# Schematic.net
KiCad netlist of a schematic drawn in EAGLE
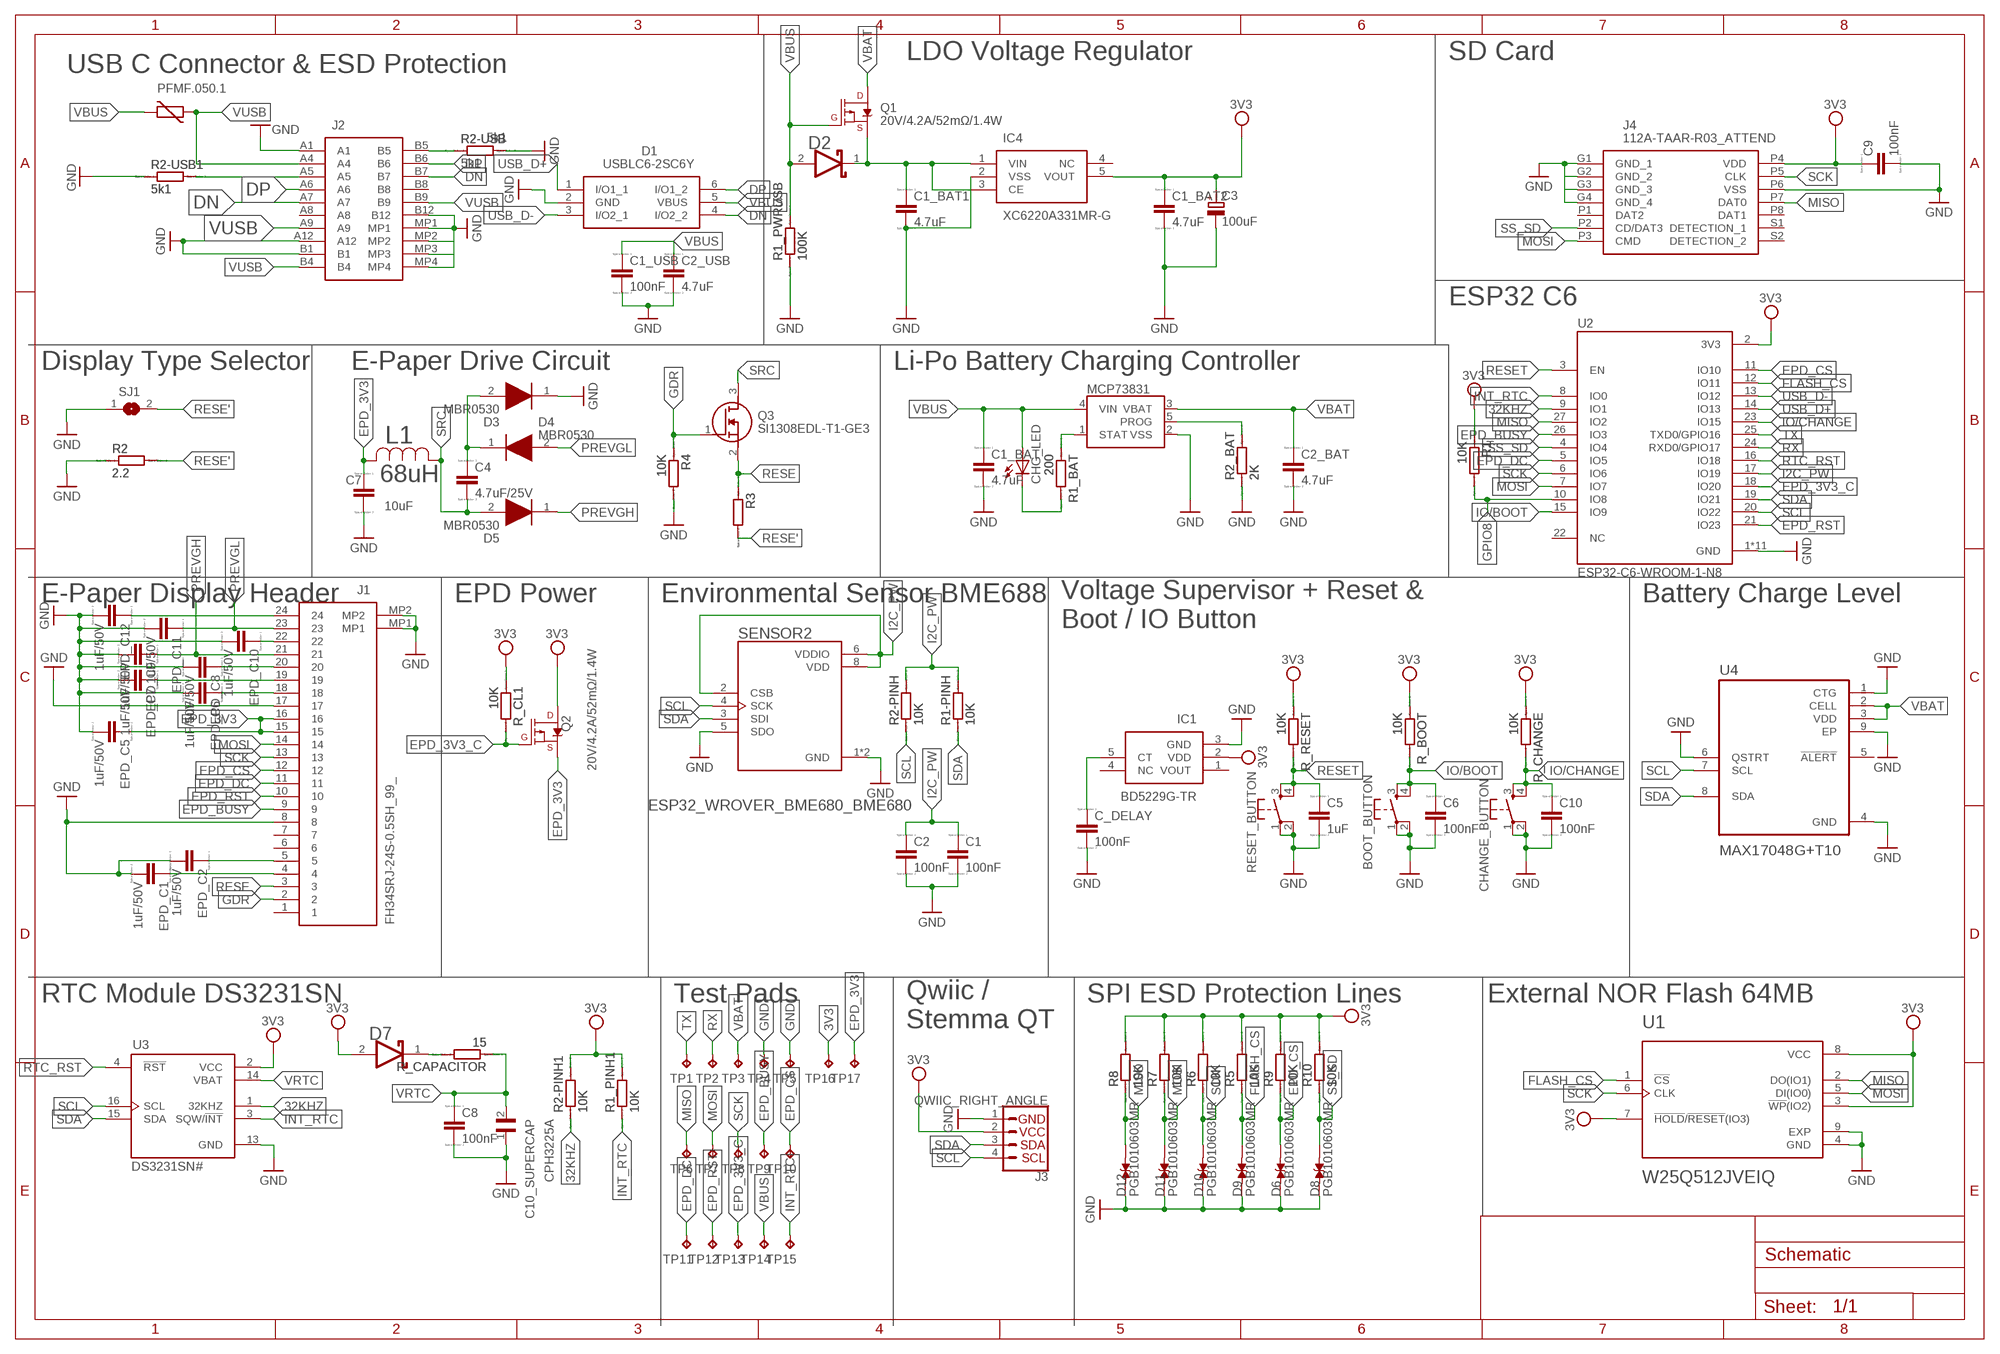
[diagram p0: schematic, sheet 1]

(export (version "E")
  (design (tool "Eeschema 10.0.6"))
  (components
    (comp (ref "BOOT_BUTTON")
      (value "BUTTON_CUSYOMV1")
      (footprint "eagle-import:MYBUTTON")
      (libsource (lib "eagle-import") (part "BUTTON_CUSYOMV1"))
    )
    (comp (ref "C1")
      (value "100nF")
      (footprint "eagle-import:ESP32_WROVER_EAGLE-LTSPICE_C0402")
      (libsource (lib "eagle-import") (part "ESP32_WROVER_EAGLE-LTSPICE_CC0402"))
    )
    (comp (ref "C1_BAT")
      (value "4.7uF")
      (footprint "eagle-import:ESP32_WROVER_EAGLE-LTSPICE_C0402")
      (libsource (lib "eagle-import") (part "ESP32_WROVER_EAGLE-LTSPICE_CC0402"))
    )
    (comp (ref "C1_BAT1")
      (value "4.7uF")
      (footprint "eagle-import:ESP32_WROVER_EAGLE-LTSPICE_C0402")
      (libsource (lib "eagle-import") (part "ESP32_WROVER_EAGLE-LTSPICE_CC0402"))
    )
    (comp (ref "C1_BAT2")
      (value "4.7uF")
      (footprint "eagle-import:ESP32_WROVER_EAGLE-LTSPICE_C0402")
      (libsource (lib "eagle-import") (part "ESP32_WROVER_EAGLE-LTSPICE_CC0402"))
    )
    (comp (ref "C1_USB")
      (value "100nF")
      (footprint "eagle-import:ESP32_WROVER_EAGLE-LTSPICE_C0402")
      (libsource (lib "eagle-import") (part "ESP32_WROVER_EAGLE-LTSPICE_CC0402"))
    )
    (comp (ref "C2")
      (value "100nF")
      (footprint "eagle-import:ESP32_WROVER_EAGLE-LTSPICE_C0402")
      (libsource (lib "eagle-import") (part "ESP32_WROVER_EAGLE-LTSPICE_CC0402"))
    )
    (comp (ref "C2_BAT")
      (value "4.7uF")
      (footprint "eagle-import:ESP32_WROVER_EAGLE-LTSPICE_C0402")
      (libsource (lib "eagle-import") (part "ESP32_WROVER_EAGLE-LTSPICE_CC0402"))
    )
    (comp (ref "C2_USB")
      (value "4.7uF")
      (footprint "eagle-import:ESP32_WROVER_EAGLE-LTSPICE_C0402")
      (libsource (lib "eagle-import") (part "ESP32_WROVER_EAGLE-LTSPICE_CC0402"))
    )
    (comp (ref "C3")
      (value "100uF")
      (footprint "eagle-import:RCL_CT3528")
      (libsource (lib "eagle-import") (part "RCL_CPOL-EUCT3528"))
    )
    (comp (ref "C4")
      (value "4.7uF/25V")
      (footprint "eagle-import:ESP32_WROVER_EAGLE-LTSPICE_C0402")
      (libsource (lib "eagle-import") (part "ESP32_WROVER_EAGLE-LTSPICE_CC0402"))
    )
    (comp (ref "C5")
      (value "1uF")
      (footprint "eagle-import:ESP32_WROVER_EAGLE-LTSPICE_C0402")
      (libsource (lib "eagle-import") (part "ESP32_WROVER_EAGLE-LTSPICE_CC0402"))
    )
    (comp (ref "C6")
      (value "100nF")
      (footprint "eagle-import:ESP32_WROVER_EAGLE-LTSPICE_C0402")
      (libsource (lib "eagle-import") (part "ESP32_WROVER_EAGLE-LTSPICE_CC0402"))
    )
    (comp (ref "C7")
      (value "10uF")
      (footprint "eagle-import:ESP32_WROVER_EAGLE-LTSPICE_C0402")
      (libsource (lib "eagle-import") (part "ESP32_WROVER_EAGLE-LTSPICE_CC0402"))
    )
    (comp (ref "C8")
      (value "100nF")
      (footprint "eagle-import:ESP32_WROVER_EAGLE-LTSPICE_C0402")
      (libsource (lib "eagle-import") (part "ESP32_WROVER_EAGLE-LTSPICE_CC0402"))
    )
    (comp (ref "C9")
      (value "100nF")
      (footprint "eagle-import:ESP32_WROVER_EAGLE-LTSPICE_C0402")
      (libsource (lib "eagle-import") (part "ESP32_WROVER_EAGLE-LTSPICE_CC0402"))
    )
    (comp (ref "C10")
      (value "100nF")
      (footprint "eagle-import:ESP32_WROVER_EAGLE-LTSPICE_C0402")
      (libsource (lib "eagle-import") (part "ESP32_WROVER_EAGLE-LTSPICE_CC0402"))
    )
    (comp (ref "C10_SUPERCAP")
      (value "CPH3225A")
      (footprint "eagle-import:CAPCP3225X100N")
      (fields (field (name "MF") "Seiko Instruments"))
      (libsource (lib "eagle-import") (part "CPH3225A"))
    )
    (comp (ref "CHANGE_BUTTON")
      (value "BUTTON_CUSYOMV1")
      (footprint "eagle-import:MYBUTTON")
      (libsource (lib "eagle-import") (part "BUTTON_CUSYOMV1"))
    )
    (comp (ref "CHG_LED")
      (value "ADAFRUIT_LEDCHIP-LED0603")
      (footprint "eagle-import:ADAFRUIT_CHIP-LED0603")
      (libsource (lib "eagle-import") (part "ADAFRUIT_LEDCHIP-LED0603"))
    )
    (comp (ref "C_DELAY")
      (value "100nF")
      (footprint "eagle-import:ESP32_WROVER_EAGLE-LTSPICE_C0402")
      (libsource (lib "eagle-import") (part "ESP32_WROVER_EAGLE-LTSPICE_CC0402"))
    )
    (comp (ref "D1")
      (value "USBLC6-2SC6Y")
      (footprint "eagle-import:SOT95P280X145-6N")
      (fields (field (name "MF") "STMicroelectronics"))
      (libsource (lib "eagle-import") (part "USBLC6-2SC6Y"))
    )
    (comp (ref "D2")
      (value "ESP32_WROVER_AVX---SD0805S020S1R0_AVX_SD0805S020S1R0_0_0AVX_SD0805S020S1R0_0_0")
      (footprint "eagle-import:ESP32_WROVER_AVX---SD0805S020S1R0_AVX_SD0805S020S1R0_0")
      (fields
        (field (name "DIGIKEY_PART_NUMBER") "478-7800-1-ND")
        (field (name "MF") "AVX")
        (field (name "MOUSER_PART_NUMBER") "581-SD0805S020S1R0")
      )
      (libsource (lib "eagle-import") (part "ESP32_WROVER_AVX---SD0805S020S1R0_AVX_SD0805S020S1R0_0_0AVX_SD0805S020S1R0_0_0"))
    )
    (comp (ref "D3")
      (value "MBR0530")
      (footprint "eagle-import:SOD3716X135N")
      (fields (field (name "MF") "ON Semiconductor"))
      (libsource (lib "eagle-import") (part "MBR0530"))
    )
    (comp (ref "D4")
      (value "MBR0530")
      (footprint "eagle-import:SOD3716X135N")
      (fields (field (name "MF") "ON Semiconductor"))
      (libsource (lib "eagle-import") (part "MBR0530"))
    )
    (comp (ref "D5")
      (value "MBR0530")
      (footprint "eagle-import:SOD3716X135N")
      (fields (field (name "MF") "ON Semiconductor"))
      (libsource (lib "eagle-import") (part "MBR0530"))
    )
    (comp (ref "D6")
      (value "PGB1010603MR")
      (footprint "eagle-import:DIOC1608X36N")
      (fields (field (name "MF") "Littelfuse Inc."))
      (libsource (lib "eagle-import") (part "PGB1010603MR"))
    )
    (comp (ref "D7")
      (value "ESP32_WROVER_AVX---SD0805S020S1R0_AVX_SD0805S020S1R0_0_0AVX_SD0805S020S1R0_0_0")
      (footprint "eagle-import:ESP32_WROVER_AVX---SD0805S020S1R0_AVX_SD0805S020S1R0_0")
      (fields
        (field (name "DIGIKEY_PART_NUMBER") "478-7800-1-ND")
        (field (name "MF") "AVX")
        (field (name "MOUSER_PART_NUMBER") "581-SD0805S020S1R0")
      )
      (libsource (lib "eagle-import") (part "ESP32_WROVER_AVX---SD0805S020S1R0_AVX_SD0805S020S1R0_0_0AVX_SD0805S020S1R0_0_0"))
    )
    (comp (ref "D8")
      (value "PGB1010603MR")
      (footprint "eagle-import:DIOC1608X36N")
      (fields (field (name "MF") "Littelfuse Inc."))
      (libsource (lib "eagle-import") (part "PGB1010603MR"))
    )
    (comp (ref "D9")
      (value "PGB1010603MR")
      (footprint "eagle-import:DIOC1608X36N")
      (fields (field (name "MF") "Littelfuse Inc."))
      (libsource (lib "eagle-import") (part "PGB1010603MR"))
    )
    (comp (ref "D10")
      (value "PGB1010603MR")
      (footprint "eagle-import:DIOC1608X36N")
      (fields (field (name "MF") "Littelfuse Inc."))
      (libsource (lib "eagle-import") (part "PGB1010603MR"))
    )
    (comp (ref "D11")
      (value "PGB1010603MR")
      (footprint "eagle-import:DIOC1608X36N")
      (fields (field (name "MF") "Littelfuse Inc."))
      (libsource (lib "eagle-import") (part "PGB1010603MR"))
    )
    (comp (ref "D12")
      (value "PGB1010603MR")
      (footprint "eagle-import:DIOC1608X36N")
      (fields (field (name "MF") "Littelfuse Inc."))
      (libsource (lib "eagle-import") (part "PGB1010603MR"))
    )
    (comp (ref "EPD_C1")
      (value "1uF/50V")
      (footprint "eagle-import:ESP32_WROVER_EAGLE-LTSPICE_C0402")
      (libsource (lib "eagle-import") (part "ESP32_WROVER_EAGLE-LTSPICE_CC0402"))
    )
    (comp (ref "EPD_C2")
      (value "1uF/50V")
      (footprint "eagle-import:ESP32_WROVER_EAGLE-LTSPICE_C0402")
      (libsource (lib "eagle-import") (part "ESP32_WROVER_EAGLE-LTSPICE_CC0402"))
    )
    (comp (ref "EPD_C5")
      (value "1uF/50V")
      (footprint "eagle-import:ESP32_WROVER_EAGLE-LTSPICE_C0402")
      (libsource (lib "eagle-import") (part "ESP32_WROVER_EAGLE-LTSPICE_CC0402"))
    )
    (comp (ref "EPD_C6")
      (value "1uF/50V")
      (footprint "eagle-import:ESP32_WROVER_EAGLE-LTSPICE_C0402")
      (libsource (lib "eagle-import") (part "ESP32_WROVER_EAGLE-LTSPICE_CC0402"))
    )
    (comp (ref "EPD_C7")
      (value "1uF/50V")
      (footprint "eagle-import:ESP32_WROVER_EAGLE-LTSPICE_C0402")
      (libsource (lib "eagle-import") (part "ESP32_WROVER_EAGLE-LTSPICE_CC0402"))
    )
    (comp (ref "EPD_C8")
      (value "1uF/50V")
      (footprint "eagle-import:ESP32_WROVER_EAGLE-LTSPICE_C0402")
      (libsource (lib "eagle-import") (part "ESP32_WROVER_EAGLE-LTSPICE_CC0402"))
    )
    (comp (ref "EPD_C9")
      (value "1uF/50V")
      (footprint "eagle-import:ESP32_WROVER_EAGLE-LTSPICE_C0402")
      (libsource (lib "eagle-import") (part "ESP32_WROVER_EAGLE-LTSPICE_CC0402"))
    )
    (comp (ref "EPD_C10")
      (value "1uF/50V")
      (footprint "eagle-import:ESP32_WROVER_EAGLE-LTSPICE_C0402")
      (libsource (lib "eagle-import") (part "ESP32_WROVER_EAGLE-LTSPICE_CC0402"))
    )
    (comp (ref "EPD_C11")
      (value "1uF/50V")
      (footprint "eagle-import:ESP32_WROVER_EAGLE-LTSPICE_C0402")
      (libsource (lib "eagle-import") (part "ESP32_WROVER_EAGLE-LTSPICE_CC0402"))
    )
    (comp (ref "EPD_C12")
      (value "1uF/50V")
      (footprint "eagle-import:ESP32_WROVER_EAGLE-LTSPICE_C0402")
      (libsource (lib "eagle-import") (part "ESP32_WROVER_EAGLE-LTSPICE_CC0402"))
    )
    (comp (ref "IC1")
      (value "BD5229G-TR")
      (footprint "eagle-import:SOT95P280X125-5N")
      (fields (field (name "MOUSER_PART_NUMBER") "755-BD5229G-TR"))
      (libsource (lib "eagle-import") (part "BD5229G-TR"))
    )
    (comp (ref "IC4")
      (value "XC6220A331MR-G")
      (footprint "eagle-import:SOT95P280X120-5N")
      (fields (field (name "MOUSER_PART_NUMBER") "865-XC6220A331MR-G"))
      (libsource (lib "eagle-import") (part "XC6220A331MR-G"))
    )
    (comp (ref "J1")
      (value "FH34SRJ-24S-0.5SH_99_")
      (footprint "eagle-import:FH34SRJ24S05SH99")
      (fields
        (field (name "MANUFACTURER_PART_NUMBER") "FH34SRJ-24S-0.5SH(99)")
        (field (name "MOUSER_PART_NUMBER") "798-FH34SRJ24S05SH99")
      )
      (libsource (lib "eagle-import") (part "FH34SRJ-24S-0.5SH_99_"))
    )
    (comp (ref "J2")
      (value "SAMACSYS_PARTS_USB4110-GF-A")
      (footprint "eagle-import:SAMACSYS_PARTS_USB4110GFA")
      (fields
        (field (name "MANUFACTURER_PART_NUMBER") "USB4110-GF-A")
        (field (name "MOUSER_PART_NUMBER") "640-USB4110-GF-A")
      )
      (libsource (lib "eagle-import") (part "SAMACSYS_PARTS_USB4110-GF-A"))
    )
    (comp (ref "J3")
      (value "QWIIC_RIGHT_ANGLE")
      (footprint "eagle-import:JST04_1MM_RA")
      (libsource (lib "eagle-import") (part "QWIIC_CONNECTORJS-1MM"))
    )
    (comp (ref "J4")
      (value "112A-TAAR-R03_ATTEND")
      (footprint "eagle-import:112ATAARR03ATTEND")
      (fields (field (name "MANUFACTURER_PART_NUMBER") "112A-TAAR-R03 ATTEND"))
      (libsource (lib "eagle-import") (part "112A-TAAR-R03_ATTEND"))
    )
    (comp (ref "L1")
      (value "68uH")
      (footprint "eagle-import:IND_4828-WE-TPC_WRE")
      (fields
        (field (name "MANUFACTURER_PART_NUMBER") "744043680")
        (field (name "COPYRIGHT") "Copyright (C) 2024 Ultra Librarian. All rights reserved.")
      )
      (libsource (lib "eagle-import") (part "744043680IND_4828-WE-TPC_WRE"))
    )
    (comp (ref "MCP73831")
      (value "ESP32_WROVER_SPARKFUN-IC-POWER_MCP73831")
      (footprint "eagle-import:ESP32_WROVER_SPARKFUN-IC-POWER_SOT23-5")
      (libsource (lib "eagle-import") (part "ESP32_WROVER_SPARKFUN-IC-POWER_MCP73831"))
    )
    (comp (ref "PFMF.050.1")
      (value "ESP32C6_VARISTORCN1812")
      (footprint "eagle-import:ESP32C6_VARISTOR_CT_CN1812")
      (libsource (lib "eagle-import") (part "ESP32C6_VARISTORCN1812"))
    )
    (comp (ref "Q1")
      (value "20V/4.2A/52mΩ/1.4W")
      (footprint "eagle-import:ESP32_WROVER_SPARKFUN-DISCRETESEMI_SOT23-3")
      (libsource (lib "eagle-import") (part "ESP32_WROVER_SPARKFUN-DISCRETESEMI_MOSFET_PCH-DMG2305UX-7"))
    )
    (comp (ref "Q2")
      (value "20V/4.2A/52mΩ/1.4W")
      (footprint "eagle-import:ESP32_WROVER_SPARKFUN-DISCRETESEMI_SOT23-3")
      (libsource (lib "eagle-import") (part "ESP32_WROVER_SPARKFUN-DISCRETESEMI_MOSFET_PCH-DMG2305UX-7"))
    )
    (comp (ref "Q3")
      (value "SI1308EDL-T1-GE3")
      (footprint "eagle-import:SOT65P210X110-3N")
      (fields (field (name "MF") "Vishay Siliconix"))
      (libsource (lib "eagle-import") (part "SI1308EDL-T1-GE3"))
    )
    (comp (ref "R1")
      (value "10K")
      (footprint "eagle-import:ESP32_WROVER_EAGLE-LTSPICE_R0402")
      (libsource (lib "eagle-import") (part "ESP32_WROVER_EAGLE-LTSPICE_RR0402"))
    )
    (comp (ref "R1-PINH")
      (value "10K")
      (footprint "eagle-import:ESP32_WROVER_EAGLE-LTSPICE_R0402")
      (libsource (lib "eagle-import") (part "ESP32_WROVER_EAGLE-LTSPICE_RR0402"))
    )
    (comp (ref "R1_BAT")
      (value "200")
      (footprint "eagle-import:ESP32_WROVER_EAGLE-LTSPICE_R0402")
      (libsource (lib "eagle-import") (part "ESP32_WROVER_EAGLE-LTSPICE_RR0402"))
    )
    (comp (ref "R1_PINH1")
      (value "10K")
      (footprint "eagle-import:ESP32_WROVER_EAGLE-LTSPICE_R0402")
      (libsource (lib "eagle-import") (part "ESP32_WROVER_EAGLE-LTSPICE_RR0402"))
    )
    (comp (ref "R1_PWRUSB")
      (value "100K")
      (footprint "eagle-import:ESP32_WROVER_EAGLE-LTSPICE_R0402")
      (libsource (lib "eagle-import") (part "ESP32_WROVER_EAGLE-LTSPICE_RR0402"))
    )
    (comp (ref "R2")
      (value "2.2")
      (footprint "eagle-import:ESP32_WROVER_EAGLE-LTSPICE_R0402")
      (libsource (lib "eagle-import") (part "ESP32_WROVER_EAGLE-LTSPICE_RR0402"))
    )
    (comp (ref "R2-PINH")
      (value "10K")
      (footprint "eagle-import:ESP32_WROVER_EAGLE-LTSPICE_R0402")
      (libsource (lib "eagle-import") (part "ESP32_WROVER_EAGLE-LTSPICE_RR0402"))
    )
    (comp (ref "R2-PINH1")
      (value "10K")
      (footprint "eagle-import:ESP32_WROVER_EAGLE-LTSPICE_R0402")
      (libsource (lib "eagle-import") (part "ESP32_WROVER_EAGLE-LTSPICE_RR0402"))
    )
    (comp (ref "R2-USB")
      (value "5k1")
      (footprint "eagle-import:ESP32_WROVER_EAGLE-LTSPICE_R0402")
      (libsource (lib "eagle-import") (part "ESP32_WROVER_EAGLE-LTSPICE_RR0402"))
    )
    (comp (ref "R2-USB1")
      (value "5k1")
      (footprint "eagle-import:ESP32_WROVER_EAGLE-LTSPICE_R0402")
      (libsource (lib "eagle-import") (part "ESP32_WROVER_EAGLE-LTSPICE_RR0402"))
    )
    (comp (ref "R2_BAT")
      (value "2K")
      (footprint "eagle-import:ESP32_WROVER_EAGLE-LTSPICE_R0402")
      (libsource (lib "eagle-import") (part "ESP32_WROVER_EAGLE-LTSPICE_RR0402"))
    )
    (comp (ref "R3")
      (value "ESP32_WROVER_EAGLE-LTSPICE_RR0402")
      (footprint "eagle-import:ESP32_WROVER_EAGLE-LTSPICE_R0402")
      (libsource (lib "eagle-import") (part "ESP32_WROVER_EAGLE-LTSPICE_RR0402"))
    )
    (comp (ref "R4")
      (value "10K")
      (footprint "eagle-import:ESP32_WROVER_EAGLE-LTSPICE_R0402")
      (libsource (lib "eagle-import") (part "ESP32_WROVER_EAGLE-LTSPICE_RR0402"))
    )
    (comp (ref "R5")
      (value "10K")
      (footprint "eagle-import:ESP32_WROVER_EAGLE-LTSPICE_R0402")
      (libsource (lib "eagle-import") (part "ESP32_WROVER_EAGLE-LTSPICE_RR0402"))
    )
    (comp (ref "R6")
      (value "10K")
      (footprint "eagle-import:ESP32_WROVER_EAGLE-LTSPICE_R0402")
      (libsource (lib "eagle-import") (part "ESP32_WROVER_EAGLE-LTSPICE_RR0402"))
    )
    (comp (ref "R7")
      (value "10K")
      (footprint "eagle-import:ESP32_WROVER_EAGLE-LTSPICE_R0402")
      (libsource (lib "eagle-import") (part "ESP32_WROVER_EAGLE-LTSPICE_RR0402"))
    )
    (comp (ref "R8")
      (value "10K")
      (footprint "eagle-import:ESP32_WROVER_EAGLE-LTSPICE_R0402")
      (libsource (lib "eagle-import") (part "ESP32_WROVER_EAGLE-LTSPICE_RR0402"))
    )
    (comp (ref "R9")
      (value "10K")
      (footprint "eagle-import:ESP32_WROVER_EAGLE-LTSPICE_R0402")
      (libsource (lib "eagle-import") (part "ESP32_WROVER_EAGLE-LTSPICE_RR0402"))
    )
    (comp (ref "R10")
      (value "10K")
      (footprint "eagle-import:ESP32_WROVER_EAGLE-LTSPICE_R0402")
      (libsource (lib "eagle-import") (part "ESP32_WROVER_EAGLE-LTSPICE_RR0402"))
    )
    (comp (ref "RESET_BUTTON")
      (value "BUTTON_CUSYOMV1")
      (footprint "eagle-import:MYBUTTON")
      (libsource (lib "eagle-import") (part "BUTTON_CUSYOMV1"))
    )
    (comp (ref "R_BOOT")
      (value "10K")
      (footprint "eagle-import:ESP32_WROVER_EAGLE-LTSPICE_R0402")
      (libsource (lib "eagle-import") (part "ESP32_WROVER_EAGLE-LTSPICE_RR0402"))
    )
    (comp (ref "R_CAPACITOR")
      (value "15")
      (footprint "eagle-import:ESP32_WROVER_EAGLE-LTSPICE_R0402")
      (libsource (lib "eagle-import") (part "ESP32_WROVER_EAGLE-LTSPICE_RR0402"))
    )
    (comp (ref "R_CHANGE")
      (value "10K")
      (footprint "eagle-import:ESP32_WROVER_EAGLE-LTSPICE_R0402")
      (libsource (lib "eagle-import") (part "ESP32_WROVER_EAGLE-LTSPICE_RR0402"))
    )
    (comp (ref "R_CL1")
      (value "10K")
      (footprint "eagle-import:ESP32_WROVER_EAGLE-LTSPICE_R0402")
      (libsource (lib "eagle-import") (part "ESP32_WROVER_EAGLE-LTSPICE_RR0402"))
    )
    (comp (ref "R_RESET")
      (value "10K")
      (footprint "eagle-import:ESP32_WROVER_EAGLE-LTSPICE_R0402")
      (libsource (lib "eagle-import") (part "ESP32_WROVER_EAGLE-LTSPICE_RR0402"))
    )
    (comp (ref "SENSOR2")
      (value "ESP32_WROVER_BME680_BME680")
      (footprint "eagle-import:ESP32_WROVER_BME680_PSON80P300X300X100-8N")
      (fields (field (name "MF") "Bosch Sensortec") (field (name "MP") "BME680"))
      (libsource (lib "eagle-import") (part "ESP32_WROVER_BME680_BME680"))
    )
    (comp (ref "SJ1") (value "SJ") (footprint "eagle-import:SJ") (libsource (lib "eagle-import") (part "SJ")))
    (comp (ref "TP1")
      (value "TPTP20R")
      (footprint "eagle-import:TP20R")
      (libsource (lib "eagle-import") (part "TPTP20R"))
    )
    (comp (ref "TP2")
      (value "TPTP20R")
      (footprint "eagle-import:TP20R")
      (libsource (lib "eagle-import") (part "TPTP20R"))
    )
    (comp (ref "TP3")
      (value "TPTP20R")
      (footprint "eagle-import:TP20R")
      (libsource (lib "eagle-import") (part "TPTP20R"))
    )
    (comp (ref "TP4")
      (value "TPTP20R")
      (footprint "eagle-import:TP20R")
      (libsource (lib "eagle-import") (part "TPTP20R"))
    )
    (comp (ref "TP5")
      (value "TPTP20R")
      (footprint "eagle-import:TP20R")
      (libsource (lib "eagle-import") (part "TPTP20R"))
    )
    (comp (ref "TP6")
      (value "TPTP20R")
      (footprint "eagle-import:TP20R")
      (libsource (lib "eagle-import") (part "TPTP20R"))
    )
    (comp (ref "TP7")
      (value "TPTP20R")
      (footprint "eagle-import:TP20R")
      (libsource (lib "eagle-import") (part "TPTP20R"))
    )
    (comp (ref "TP8")
      (value "TPTP20R")
      (footprint "eagle-import:TP20R")
      (libsource (lib "eagle-import") (part "TPTP20R"))
    )
    (comp (ref "TP9")
      (value "TPTP20R")
      (footprint "eagle-import:TP20R")
      (libsource (lib "eagle-import") (part "TPTP20R"))
    )
    (comp (ref "TP10")
      (value "TPTP20R")
      (footprint "eagle-import:TP20R")
      (libsource (lib "eagle-import") (part "TPTP20R"))
    )
    (comp (ref "TP11")
      (value "TPTP20R")
      (footprint "eagle-import:TP20R")
      (libsource (lib "eagle-import") (part "TPTP20R"))
    )
    (comp (ref "TP12")
      (value "TPTP20R")
      (footprint "eagle-import:TP20R")
      (libsource (lib "eagle-import") (part "TPTP20R"))
    )
    (comp (ref "TP13")
      (value "TPTP20R")
      (footprint "eagle-import:TP20R")
      (libsource (lib "eagle-import") (part "TPTP20R"))
    )
    (comp (ref "TP14")
      (value "TPTP20R")
      (footprint "eagle-import:TP20R")
      (libsource (lib "eagle-import") (part "TPTP20R"))
    )
    (comp (ref "TP15")
      (value "TPTP20R")
      (footprint "eagle-import:TP20R")
      (libsource (lib "eagle-import") (part "TPTP20R"))
    )
    (comp (ref "TP16")
      (value "TPTP20R")
      (footprint "eagle-import:TP20R")
      (libsource (lib "eagle-import") (part "TPTP20R"))
    )
    (comp (ref "TP17")
      (value "TPTP20R")
      (footprint "eagle-import:TP20R")
      (libsource (lib "eagle-import") (part "TPTP20R"))
    )
    (comp (ref "U1")
      (value "W25Q512JVEIQ")
      (footprint "eagle-import:SON127P600X800X80-9N")
      (fields (field (name "MF") "Winbond Electronics"))
      (libsource (lib "eagle-import") (part "W25Q512JVEIQ"))
    )
    (comp (ref "U2")
      (value "ESP32-C6-WROOM-1-N8")
      (footprint "eagle-import:XCVR_ESP32-C6-WROOM-1-N8")
      (fields (field (name "MF") "Espressif Systems"))
      (libsource (lib "eagle-import") (part "ESP32-C6-WROOM-1-N8"))
    )
    (comp (ref "U3")
      (value "DS3231SN#")
      (footprint "eagle-import:SOIC127P1032X265-16N")
      (fields (field (name "MF") "Analog Devices"))
      (libsource (lib "eagle-import") (part "DS3231SN#"))
    )
    (comp (ref "U4")
      (value "MAX17048G+T10")
      (footprint "eagle-import:SON50P200X200X80-9N")
      (fields (field (name "MF") "Analog Devices"))
      (libsource (lib "eagle-import") (part "MAX17048G+T10"))
    )
  )
  (nets
    (net (code "1") (name "3V3") (class "Default")
      (node (ref "C1_BAT2") (pin "1") (pinfunction "1_1") (pintype "passive"))
      (node (ref "C3") (pin "+") (pinfunction "+_+") (pintype "passive"))
      (node (ref "C9") (pin "1") (pinfunction "1_1") (pintype "passive"))
      (node (ref "D7") (pin "2") (pinfunction "ANODE_2") (pintype "bidirectional"))
      (node (ref "IC1") (pin "2") (pinfunction "VDD_2") (pintype "bidirectional"))
      (node (ref "IC4") (pin "5") (pinfunction "VOUT_5") (pintype "bidirectional"))
      (node (ref "J3") (pin "2") (pinfunction "2_2") (pintype "power_in"))
      (node (ref "J4") (pin "P4") (pinfunction "VDD_P4") (pintype "bidirectional"))
      (node (ref "Q2") (pin "3") (pinfunction "D_3") (pintype "bidirectional"))
      (node (ref "R1") (pin "1") (pinfunction "1_1") (pintype "passive"))
      (node (ref "R10") (pin "2") (pinfunction "2_2") (pintype "passive"))
      (node (ref "R1_PINH1") (pin "2") (pinfunction "2_2") (pintype "passive"))
      (node (ref "R2-PINH1") (pin "2") (pinfunction "2_2") (pintype "passive"))
      (node (ref "R5") (pin "2") (pinfunction "2_2") (pintype "passive"))
      (node (ref "R6") (pin "2") (pinfunction "2_2") (pintype "passive"))
      (node (ref "R7") (pin "2") (pinfunction "2_2") (pintype "passive"))
      (node (ref "R8") (pin "2") (pinfunction "2_2") (pintype "passive"))
      (node (ref "R9") (pin "2") (pinfunction "2_2") (pintype "passive"))
      (node (ref "R_BOOT") (pin "1") (pinfunction "1_1") (pintype "passive"))
      (node (ref "R_CHANGE") (pin "1") (pinfunction "1_1") (pintype "passive"))
      (node (ref "R_CL1") (pin "1") (pinfunction "1_1") (pintype "passive"))
      (node (ref "R_RESET") (pin "1") (pinfunction "1_1") (pintype "passive"))
      (node (ref "TP16") (pin "TP") (pinfunction "TP_TP") (pintype "input"))
      (node (ref "U1") (pin "3") (pinfunction "~{WP}(IO2)_3") (pintype "bidirectional"))
      (node (ref "U1") (pin "7") (pinfunction "~{HOLD}/~{RESET}(IO3)_7") (pintype "bidirectional"))
      (node (ref "U1") (pin "8") (pinfunction "VCC_8") (pintype "power_in"))
      (node (ref "U2") (pin "2") (pinfunction "3V3_2") (pintype "power_in"))
      (node (ref "U3") (pin "2") (pinfunction "VCC_2") (pintype "power_in"))
    )
    (net (code "2") (name "32KHZ") (class "Default")
      (node (ref "R2-PINH1") (pin "1") (pinfunction "1_1") (pintype "passive"))
      (node (ref "U2") (pin "9") (pinfunction "IO1_9") (pintype "bidirectional"))
      (node (ref "U3") (pin "1") (pinfunction "32KHZ_1") (pintype "output"))
    )
    (net (code "3") (name "DN") (class "Default")
      (node (ref "D1") (pin "4") (pinfunction "I/O2_2_4") (pintype "bidirectional"))
      (node (ref "J2") (pin "A7") (pinfunction "A7_A7") (pintype "bidirectional"))
      (node (ref "J2") (pin "B7") (pinfunction "B7_B7") (pintype "bidirectional"))
    )
    (net (code "4") (name "DP") (class "Default")
      (node (ref "D1") (pin "6") (pinfunction "I/O1_2_6") (pintype "bidirectional"))
      (node (ref "J2") (pin "A6") (pinfunction "A6_A6") (pintype "bidirectional"))
      (node (ref "J2") (pin "B6") (pinfunction "B6_B6") (pintype "bidirectional"))
    )
    (net (code "5") (name "EPD_3V3") (class "Default")
      (node (ref "C7") (pin "1") (pinfunction "1_1") (pintype "passive"))
      (node (ref "EPD_C5") (pin "1") (pinfunction "1_1") (pintype "passive"))
      (node (ref "J1") (pin "15") (pinfunction "15_15") (pintype "bidirectional"))
      (node (ref "J1") (pin "16") (pinfunction "16_16") (pintype "bidirectional"))
      (node (ref "L1") (pin "2") (pinfunction "2_2") (pintype "passive"))
      (node (ref "Q2") (pin "2") (pinfunction "S_2") (pintype "bidirectional"))
      (node (ref "TP17") (pin "TP") (pinfunction "TP_TP") (pintype "input"))
    )
    (net (code "6") (name "EPD_3V3_C") (class "Default")
      (node (ref "Q2") (pin "1") (pinfunction "G_1") (pintype "bidirectional"))
      (node (ref "R_CL1") (pin "2") (pinfunction "2_2") (pintype "passive"))
      (node (ref "TP13") (pin "TP") (pinfunction "TP_TP") (pintype "input"))
      (node (ref "U2") (pin "18") (pinfunction "IO20_18") (pintype "bidirectional"))
    )
    (net (code "7") (name "EPD_BUSY") (class "Default")
      (node (ref "J1") (pin "9") (pinfunction "9_9") (pintype "bidirectional"))
      (node (ref "TP9") (pin "TP") (pinfunction "TP_TP") (pintype "input"))
      (node (ref "U2") (pin "26") (pinfunction "IO3_26") (pintype "bidirectional"))
    )
    (net (code "8") (name "EPD_CS") (class "Default")
      (node (ref "D6") (pin "2") (pinfunction "2_2") (pintype "passive"))
      (node (ref "J1") (pin "12") (pinfunction "12_12") (pintype "bidirectional"))
      (node (ref "R9") (pin "1") (pinfunction "1_1") (pintype "passive"))
      (node (ref "TP10") (pin "TP") (pinfunction "TP_TP") (pintype "input"))
      (node (ref "U2") (pin "11") (pinfunction "IO10_11") (pintype "bidirectional"))
    )
    (net (code "9") (name "EPD_DC") (class "Default")
      (node (ref "J1") (pin "11") (pinfunction "11_11") (pintype "bidirectional"))
      (node (ref "TP11") (pin "TP") (pinfunction "TP_TP") (pintype "input"))
      (node (ref "U2") (pin "5") (pinfunction "IO5_5") (pintype "bidirectional"))
    )
    (net (code "10") (name "EPD_RST") (class "Default")
      (node (ref "J1") (pin "10") (pinfunction "10_10") (pintype "bidirectional"))
      (node (ref "TP12") (pin "TP") (pinfunction "TP_TP") (pintype "input"))
      (node (ref "U2") (pin "21") (pinfunction "IO23_21") (pintype "bidirectional"))
    )
    (net (code "11") (name "FLASH_CS") (class "Default")
      (node (ref "D9") (pin "2") (pinfunction "2_2") (pintype "passive"))
      (node (ref "R5") (pin "1") (pinfunction "1_1") (pintype "passive"))
      (node (ref "U1") (pin "1") (pinfunction "~{CS}_1") (pintype "input"))
      (node (ref "U2") (pin "12") (pinfunction "IO11_12") (pintype "bidirectional"))
    )
    (net (code "12") (name "GDR") (class "Default")
      (node (ref "J1") (pin "2") (pinfunction "2_2") (pintype "bidirectional"))
      (node (ref "Q3") (pin "1") (pinfunction "G_1") (pintype "bidirectional"))
      (node (ref "R4") (pin "1") (pinfunction "1_1") (pintype "passive"))
    )
    (net (code "13") (name "GND") (class "Default")
      (node (ref "BOOT_BUTTON") (pin "1") (pinfunction "1_1") (pintype "passive"))
      (node (ref "BOOT_BUTTON") (pin "2") (pinfunction "2_2") (pintype "passive"))
      (node (ref "C1") (pin "2") (pinfunction "2_2") (pintype "passive"))
      (node (ref "C10") (pin "2") (pinfunction "2_2") (pintype "passive"))
      (node (ref "C10_SUPERCAP") (pin "1") (pinfunction "1_1") (pintype "passive"))
      (node (ref "C1_BAT") (pin "2") (pinfunction "2_2") (pintype "passive"))
      (node (ref "C1_BAT1") (pin "2") (pinfunction "2_2") (pintype "passive"))
      (node (ref "C1_BAT2") (pin "2") (pinfunction "2_2") (pintype "passive"))
      (node (ref "C1_USB") (pin "2") (pinfunction "2_2") (pintype "passive"))
      (node (ref "C2") (pin "2") (pinfunction "2_2") (pintype "passive"))
      (node (ref "C2_BAT") (pin "2") (pinfunction "2_2") (pintype "passive"))
      (node (ref "C2_USB") (pin "2") (pinfunction "2_2") (pintype "passive"))
      (node (ref "C3") (pin "-") (pinfunction "-_-") (pintype "passive"))
      (node (ref "C5") (pin "2") (pinfunction "2_2") (pintype "passive"))
      (node (ref "C6") (pin "2") (pinfunction "2_2") (pintype "passive"))
      (node (ref "C7") (pin "2") (pinfunction "2_2") (pintype "passive"))
      (node (ref "C8") (pin "2") (pinfunction "2_2") (pintype "passive"))
      (node (ref "C9") (pin "2") (pinfunction "2_2") (pintype "passive"))
      (node (ref "CHANGE_BUTTON") (pin "1") (pinfunction "1_1") (pintype "passive"))
      (node (ref "CHANGE_BUTTON") (pin "2") (pinfunction "2_2") (pintype "passive"))
      (node (ref "C_DELAY") (pin "2") (pinfunction "2_2") (pintype "passive"))
      (node (ref "D1") (pin "2") (pinfunction "GND_2") (pintype "bidirectional"))
      (node (ref "D10") (pin "1") (pinfunction "1_1") (pintype "passive"))
      (node (ref "D11") (pin "1") (pinfunction "1_1") (pintype "passive"))
      (node (ref "D12") (pin "1") (pinfunction "1_1") (pintype "passive"))
      (node (ref "D3") (pin "1") (pinfunction "K_1") (pintype "bidirectional"))
      (node (ref "D6") (pin "1") (pinfunction "1_1") (pintype "passive"))
      (node (ref "D8") (pin "1") (pinfunction "1_1") (pintype "passive"))
      (node (ref "D9") (pin "1") (pinfunction "1_1") (pintype "passive"))
      (node (ref "EPD_C1") (pin "2") (pinfunction "2_2") (pintype "passive"))
      (node (ref "EPD_C10") (pin "2") (pinfunction "2_2") (pintype "passive"))
      (node (ref "EPD_C11") (pin "2") (pinfunction "2_2") (pintype "passive"))
      (node (ref "EPD_C12") (pin "2") (pinfunction "2_2") (pintype "passive"))
      (node (ref "EPD_C2") (pin "2") (pinfunction "2_2") (pintype "passive"))
      (node (ref "EPD_C5") (pin "2") (pinfunction "2_2") (pintype "passive"))
      (node (ref "EPD_C6") (pin "2") (pinfunction "2_2") (pintype "passive"))
      (node (ref "EPD_C7") (pin "2") (pinfunction "2_2") (pintype "passive"))
      (node (ref "EPD_C8") (pin "2") (pinfunction "2_2") (pintype "passive"))
      (node (ref "EPD_C9") (pin "2") (pinfunction "2_2") (pintype "passive"))
      (node (ref "IC1") (pin "3") (pinfunction "GND_3") (pintype "bidirectional"))
      (node (ref "IC4") (pin "2") (pinfunction "VSS_2") (pintype "bidirectional"))
      (node (ref "J1") (pin "17") (pinfunction "17_17") (pintype "bidirectional"))
      (node (ref "J1") (pin "8") (pinfunction "8_8") (pintype "bidirectional"))
      (node (ref "J1") (pin "MP1") (pinfunction "MP1_MP1") (pintype "bidirectional"))
      (node (ref "J1") (pin "MP2") (pinfunction "MP2_MP2") (pintype "bidirectional"))
      (node (ref "J2") (pin "A1") (pinfunction "A1_A1") (pintype "bidirectional"))
      (node (ref "J2") (pin "A12") (pinfunction "A12_A12") (pintype "bidirectional"))
      (node (ref "J2") (pin "B1") (pinfunction "B1_B1") (pintype "bidirectional"))
      (node (ref "J2") (pin "B12") (pinfunction "B12_B12") (pintype "bidirectional"))
      (node (ref "J2") (pin "MP1") (pinfunction "MP1_MP1") (pintype "bidirectional"))
      (node (ref "J2") (pin "MP2") (pinfunction "MP2_MP2") (pintype "bidirectional"))
      (node (ref "J2") (pin "MP3") (pinfunction "MP3_MP3") (pintype "bidirectional"))
      (node (ref "J2") (pin "MP4") (pinfunction "MP4_MP4") (pintype "bidirectional"))
      (node (ref "J3") (pin "1") (pinfunction "1_1") (pintype "power_in"))
      (node (ref "J4") (pin "G1") (pinfunction "GND_1_G1") (pintype "bidirectional"))
      (node (ref "J4") (pin "G2") (pinfunction "GND_2_G2") (pintype "bidirectional"))
      (node (ref "J4") (pin "G3") (pinfunction "GND_3_G3") (pintype "bidirectional"))
      (node (ref "J4") (pin "G4") (pinfunction "GND_4_G4") (pintype "bidirectional"))
      (node (ref "J4") (pin "P6") (pinfunction "VSS_P6") (pintype "bidirectional"))
      (node (ref "MCP73831") (pin "2") (pinfunction "VSS_2") (pintype "power_in"))
      (node (ref "R1_PWRUSB") (pin "1") (pinfunction "1_1") (pintype "passive"))
      (node (ref "R2") (pin "1") (pinfunction "1_1") (pintype "passive"))
      (node (ref "R2-USB") (pin "2") (pinfunction "2_2") (pintype "passive"))
      (node (ref "R2-USB1") (pin "1") (pinfunction "1_1") (pintype "passive"))
      (node (ref "R2_BAT") (pin "1") (pinfunction "1_1") (pintype "passive"))
      (node (ref "R4") (pin "2") (pinfunction "2_2") (pintype "passive"))
      (node (ref "RESET_BUTTON") (pin "1") (pinfunction "1_1") (pintype "passive"))
      (node (ref "RESET_BUTTON") (pin "2") (pinfunction "2_2") (pintype "passive"))
      (node (ref "SENSOR2") (pin "1") (pinfunction "GND_1") (pintype "power_in"))
      (node (ref "SENSOR2") (pin "5") (pinfunction "SDO_5") (pintype "bidirectional"))
      (node (ref "SENSOR2") (pin "7") (pinfunction "GND_7") (pintype "power_in"))
      (node (ref "SJ1") (pin "1") (pinfunction "1_1") (pintype "passive"))
      (node (ref "TP4") (pin "TP") (pinfunction "TP_TP") (pintype "input"))
      (node (ref "TP5") (pin "TP") (pinfunction "TP_TP") (pintype "input"))
      (node (ref "U1") (pin "4") (pinfunction "GND_4") (pintype "power_in"))
      (node (ref "U1") (pin "9") (pinfunction "EXP_9") (pintype "passive"))
      (node (ref "U2") (pin "1") (pinfunction "GND_1") (pintype "power_in"))
      (node (ref "U2") (pin "28") (pinfunction "GND_28") (pintype "power_in"))
      (node (ref "U2") (pin "29_1") (pinfunction "GND_29_1") (pintype "power_in"))
      (node (ref "U2") (pin "29_2") (pinfunction "GND_29_2") (pintype "power_in"))
      (node (ref "U2") (pin "29_3") (pinfunction "GND_29_3") (pintype "power_in"))
      (node (ref "U2") (pin "29_4") (pinfunction "GND_29_4") (pintype "power_in"))
      (node (ref "U2") (pin "29_5") (pinfunction "GND_29_5") (pintype "power_in"))
      (node (ref "U2") (pin "29_6") (pinfunction "GND_29_6") (pintype "power_in"))
      (node (ref "U2") (pin "29_7") (pinfunction "GND_29_7") (pintype "power_in"))
      (node (ref "U2") (pin "29_8") (pinfunction "GND_29_8") (pintype "power_in"))
      (node (ref "U2") (pin "29_9") (pinfunction "GND_29_9") (pintype "power_in"))
      (node (ref "U3") (pin "13") (pinfunction "GND_13") (pintype "power_in"))
      (node (ref "U4") (pin "1") (pinfunction "CTG_1") (pintype "power_in"))
      (node (ref "U4") (pin "4") (pinfunction "GND_4") (pintype "power_in"))
      (node (ref "U4") (pin "6") (pinfunction "QSTRT_6") (pintype "input"))
      (node (ref "U4") (pin "9") (pinfunction "EP_9") (pintype "power_in"))
    )
    (net (code "14") (name "GPIO8") (class "Default")
      (node (ref "R1") (pin "2") (pinfunction "2_2") (pintype "passive"))
      (node (ref "U2") (pin "10") (pinfunction "IO8_10") (pintype "bidirectional"))
    )
    (net (code "15") (name "I2C_PW") (class "Default")
      (node (ref "C1") (pin "1") (pinfunction "1_1") (pintype "passive"))
      (node (ref "C2") (pin "1") (pinfunction "1_1") (pintype "passive"))
      (node (ref "R1-PINH") (pin "2") (pinfunction "2_2") (pintype "passive"))
      (node (ref "R2-PINH") (pin "2") (pinfunction "2_2") (pintype "passive"))
      (node (ref "SENSOR2") (pin "2") (pinfunction "CSB_2") (pintype "input"))
      (node (ref "SENSOR2") (pin "6") (pinfunction "VDDIO_6") (pintype "power_in"))
      (node (ref "SENSOR2") (pin "8") (pinfunction "VDD_8") (pintype "power_in"))
      (node (ref "U2") (pin "17") (pinfunction "IO19_17") (pintype "bidirectional"))
    )
    (net (code "16") (name "INT_RTC") (class "Default")
      (node (ref "R1_PINH1") (pin "1") (pinfunction "1_1") (pintype "passive"))
      (node (ref "TP15") (pin "TP") (pinfunction "TP_TP") (pintype "input"))
      (node (ref "U2") (pin "8") (pinfunction "IO0_8") (pintype "bidirectional"))
      (node (ref "U3") (pin "3") (pinfunction "SQW/~{INT}_3") (pintype "output"))
    )
    (net (code "17") (name "IO{slash}BOOT") (class "Default")
      (node (ref "BOOT_BUTTON") (pin "3") (pinfunction "3_3") (pintype "passive"))
      (node (ref "BOOT_BUTTON") (pin "4") (pinfunction "4_4") (pintype "passive"))
      (node (ref "C6") (pin "1") (pinfunction "1_1") (pintype "passive"))
      (node (ref "R_BOOT") (pin "2") (pinfunction "2_2") (pintype "passive"))
      (node (ref "U2") (pin "15") (pinfunction "IO9_15") (pintype "bidirectional"))
    )
    (net (code "18") (name "IO{slash}CHANGE") (class "Default")
      (node (ref "C10") (pin "1") (pinfunction "1_1") (pintype "passive"))
      (node (ref "CHANGE_BUTTON") (pin "3") (pinfunction "3_3") (pintype "passive"))
      (node (ref "CHANGE_BUTTON") (pin "4") (pinfunction "4_4") (pintype "passive"))
      (node (ref "R_CHANGE") (pin "2") (pinfunction "2_2") (pintype "passive"))
      (node (ref "U2") (pin "23") (pinfunction "IO15_23") (pintype "bidirectional"))
    )
    (net (code "19") (name "MISO") (class "Default")
      (node (ref "D12") (pin "2") (pinfunction "2_2") (pintype "passive"))
      (node (ref "J4") (pin "P7") (pinfunction "DAT0_P7") (pintype "bidirectional"))
      (node (ref "R8") (pin "1") (pinfunction "1_1") (pintype "passive"))
      (node (ref "TP6") (pin "TP") (pinfunction "TP_TP") (pintype "input"))
      (node (ref "U1") (pin "2") (pinfunction "DO(IO1)_2") (pintype "bidirectional"))
      (node (ref "U2") (pin "27") (pinfunction "IO2_27") (pintype "bidirectional"))
    )
    (net (code "20") (name "MOSI") (class "Default")
      (node (ref "D11") (pin "2") (pinfunction "2_2") (pintype "passive"))
      (node (ref "J1") (pin "14") (pinfunction "14_14") (pintype "bidirectional"))
      (node (ref "J4") (pin "P3") (pinfunction "CMD_P3") (pintype "bidirectional"))
      (node (ref "R7") (pin "1") (pinfunction "1_1") (pintype "passive"))
      (node (ref "TP7") (pin "TP") (pinfunction "TP_TP") (pintype "input"))
      (node (ref "U1") (pin "5") (pinfunction "DI(IO0)_5") (pintype "bidirectional"))
      (node (ref "U2") (pin "7") (pinfunction "IO7_7") (pintype "bidirectional"))
    )
    (net (code "21") (name "Net-(CHG_LED-PadC)") (class "Default")
      (node (ref "CHG_LED") (pin "C") (pinfunction "C_C") (pintype "passive"))
      (node (ref "R1_BAT") (pin "2") (pinfunction "2_2") (pintype "passive"))
    )
    (net (code "22") (name "Net-(D2-CATHODE)") (class "Default")
      (node (ref "C1_BAT1") (pin "1") (pinfunction "1_1") (pintype "passive"))
      (node (ref "D2") (pin "1") (pinfunction "CATHODE_1") (pintype "bidirectional"))
      (node (ref "IC4") (pin "1") (pinfunction "VIN_1") (pintype "bidirectional"))
      (node (ref "IC4") (pin "3") (pinfunction "CE_3") (pintype "bidirectional"))
      (node (ref "Q1") (pin "2") (pinfunction "S_2") (pintype "bidirectional"))
    )
    (net (code "23") (name "Net-(D3-A)") (class "Default")
      (node (ref "C4") (pin "1") (pinfunction "1_1") (pintype "passive"))
      (node (ref "D3") (pin "2") (pinfunction "A_2") (pintype "bidirectional"))
      (node (ref "D4") (pin "1") (pinfunction "K_1") (pintype "bidirectional"))
    )
    (net (code "24") (name "Net-(D7-CATHODE)") (class "Default")
      (node (ref "D7") (pin "1") (pinfunction "CATHODE_1") (pintype "bidirectional"))
      (node (ref "R_CAPACITOR") (pin "2") (pinfunction "2_2") (pintype "passive"))
    )
    (net (code "25") (name "Net-(EPD_C1-Pad1)") (class "Default")
      (node (ref "EPD_C1") (pin "1") (pinfunction "1_1") (pintype "passive"))
      (node (ref "J1") (pin "4") (pinfunction "4_4") (pintype "bidirectional"))
    )
    (net (code "26") (name "Net-(EPD_C2-Pad1)") (class "Default")
      (node (ref "EPD_C2") (pin "1") (pinfunction "1_1") (pintype "passive"))
      (node (ref "J1") (pin "5") (pinfunction "5_5") (pintype "bidirectional"))
    )
    (net (code "27") (name "Net-(EPD_C6-Pad1)") (class "Default")
      (node (ref "EPD_C6") (pin "1") (pinfunction "1_1") (pintype "passive"))
      (node (ref "J1") (pin "18") (pinfunction "18_18") (pintype "bidirectional"))
    )
    (net (code "28") (name "Net-(EPD_C7-Pad1)") (class "Default")
      (node (ref "EPD_C7") (pin "1") (pinfunction "1_1") (pintype "passive"))
      (node (ref "J1") (pin "19") (pinfunction "19_19") (pintype "bidirectional"))
    )
    (net (code "29") (name "Net-(EPD_C8-Pad1)") (class "Default")
      (node (ref "EPD_C8") (pin "1") (pinfunction "1_1") (pintype "passive"))
      (node (ref "J1") (pin "20") (pinfunction "20_20") (pintype "bidirectional"))
    )
    (net (code "30") (name "Net-(EPD_C10-Pad1)") (class "Default")
      (node (ref "EPD_C10") (pin "1") (pinfunction "1_1") (pintype "passive"))
      (node (ref "J1") (pin "22") (pinfunction "22_22") (pintype "bidirectional"))
    )
    (net (code "31") (name "Net-(EPD_C12-Pad1)") (class "Default")
      (node (ref "EPD_C12") (pin "1") (pinfunction "1_1") (pintype "passive"))
      (node (ref "J1") (pin "24") (pinfunction "24_24") (pintype "bidirectional"))
    )
    (net (code "32") (name "Net-(IC1-CT)") (class "Default")
      (node (ref "C_DELAY") (pin "1") (pinfunction "1_1") (pintype "passive"))
      (node (ref "IC1") (pin "5") (pinfunction "CT_5") (pintype "bidirectional"))
    )
    (net (code "33") (name "Net-(J2-PadA5)") (class "Default")
      (node (ref "J2") (pin "A5") (pinfunction "A5_A5") (pintype "bidirectional"))
      (node (ref "R2-USB1") (pin "2") (pinfunction "2_2") (pintype "passive"))
    )
    (net (code "34") (name "Net-(J2-PadB5)") (class "Default")
      (node (ref "J2") (pin "B5") (pinfunction "B5_B5") (pintype "bidirectional"))
      (node (ref "R2-USB") (pin "1") (pinfunction "1_1") (pintype "passive"))
    )
    (net (code "35") (name "Net-(MCP73831-PROG)") (class "Default")
      (node (ref "MCP73831") (pin "5") (pinfunction "PROG_5") (pintype "input"))
      (node (ref "R2_BAT") (pin "2") (pinfunction "2_2") (pintype "passive"))
    )
    (net (code "36") (name "Net-(MCP73831-STAT)") (class "Default")
      (node (ref "MCP73831") (pin "1") (pinfunction "STAT_1") (pintype "output"))
      (node (ref "R1_BAT") (pin "1") (pinfunction "1_1") (pintype "passive"))
    )
    (net (code "37") (name "PREVGH") (class "Default")
      (node (ref "D5") (pin "1") (pinfunction "K_1") (pintype "bidirectional"))
      (node (ref "EPD_C9") (pin "1") (pinfunction "1_1") (pintype "passive"))
      (node (ref "J1") (pin "21") (pinfunction "21_21") (pintype "bidirectional"))
    )
    (net (code "38") (name "PREVGL") (class "Default")
      (node (ref "D4") (pin "2") (pinfunction "A_2") (pintype "bidirectional"))
      (node (ref "EPD_C11") (pin "1") (pinfunction "1_1") (pintype "passive"))
      (node (ref "J1") (pin "23") (pinfunction "23_23") (pintype "bidirectional"))
    )
    (net (code "39") (name "RESE") (class "Default")
      (node (ref "J1") (pin "3") (pinfunction "3_3") (pintype "bidirectional"))
      (node (ref "Q3") (pin "2") (pinfunction "S_2") (pintype "bidirectional"))
      (node (ref "R3") (pin "1") (pinfunction "1_1") (pintype "passive"))
    )
    (net (code "40") (name "RESE'") (class "Default")
      (node (ref "R2") (pin "2") (pinfunction "2_2") (pintype "passive"))
      (node (ref "R3") (pin "2") (pinfunction "2_2") (pintype "passive"))
      (node (ref "SJ1") (pin "2") (pinfunction "2_2") (pintype "passive"))
    )
    (net (code "41") (name "RESET") (class "Default")
      (node (ref "C5") (pin "1") (pinfunction "1_1") (pintype "passive"))
      (node (ref "RESET_BUTTON") (pin "3") (pinfunction "3_3") (pintype "passive"))
      (node (ref "RESET_BUTTON") (pin "4") (pinfunction "4_4") (pintype "passive"))
      (node (ref "R_RESET") (pin "2") (pinfunction "2_2") (pintype "passive"))
      (node (ref "U2") (pin "3") (pinfunction "EN_3") (pintype "input"))
    )
    (net (code "42") (name "RTC_RST") (class "Default")
      (node (ref "U2") (pin "16") (pinfunction "IO18_16") (pintype "bidirectional"))
      (node (ref "U3") (pin "4") (pinfunction "~{RST}_4") (pintype "input"))
    )
    (net (code "43") (name "RX") (class "Default")
      (node (ref "TP2") (pin "TP") (pinfunction "TP_TP") (pintype "input"))
      (node (ref "U2") (pin "24") (pinfunction "RXD0/GPIO17_24") (pintype "bidirectional"))
    )
    (net (code "44") (name "SCK") (class "Default")
      (node (ref "D10") (pin "2") (pinfunction "2_2") (pintype "passive"))
      (node (ref "J1") (pin "13") (pinfunction "13_13") (pintype "bidirectional"))
      (node (ref "J4") (pin "P5") (pinfunction "CLK_P5") (pintype "bidirectional"))
      (node (ref "R6") (pin "1") (pinfunction "1_1") (pintype "passive"))
      (node (ref "TP8") (pin "TP") (pinfunction "TP_TP") (pintype "input"))
      (node (ref "U1") (pin "6") (pinfunction "CLK_6") (pintype "input"))
      (node (ref "U2") (pin "6") (pinfunction "IO6_6") (pintype "bidirectional"))
    )
    (net (code "45") (name "SCL") (class "Default")
      (node (ref "J3") (pin "4") (pinfunction "4_4") (pintype "passive"))
      (node (ref "R2-PINH") (pin "1") (pinfunction "1_1") (pintype "passive"))
      (node (ref "SENSOR2") (pin "4") (pinfunction "SCK_4") (pintype "input"))
      (node (ref "U2") (pin "20") (pinfunction "IO22_20") (pintype "bidirectional"))
      (node (ref "U3") (pin "16") (pinfunction "SCL_16") (pintype "input"))
      (node (ref "U4") (pin "7") (pinfunction "SCL_7") (pintype "input"))
    )
    (net (code "46") (name "SDA") (class "Default")
      (node (ref "J3") (pin "3") (pinfunction "3_3") (pintype "passive"))
      (node (ref "R1-PINH") (pin "1") (pinfunction "1_1") (pintype "passive"))
      (node (ref "SENSOR2") (pin "3") (pinfunction "SDI_3") (pintype "bidirectional"))
      (node (ref "U2") (pin "19") (pinfunction "IO21_19") (pintype "bidirectional"))
      (node (ref "U3") (pin "15") (pinfunction "SDA_15") (pintype "bidirectional"))
      (node (ref "U4") (pin "8") (pinfunction "SDA_8") (pintype "bidirectional"))
    )
    (net (code "47") (name "SRC") (class "Default")
      (node (ref "C4") (pin "2") (pinfunction "2_2") (pintype "passive"))
      (node (ref "D5") (pin "2") (pinfunction "A_2") (pintype "bidirectional"))
      (node (ref "L1") (pin "1") (pinfunction "1_1") (pintype "passive"))
      (node (ref "Q3") (pin "3") (pinfunction "D_3") (pintype "bidirectional"))
    )
    (net (code "48") (name "SS_SD") (class "Default")
      (node (ref "D8") (pin "2") (pinfunction "2_2") (pintype "passive"))
      (node (ref "J4") (pin "P2") (pinfunction "CD/DAT3_P2") (pintype "bidirectional"))
      (node (ref "R10") (pin "1") (pinfunction "1_1") (pintype "passive"))
      (node (ref "U2") (pin "4") (pinfunction "IO4_4") (pintype "bidirectional"))
    )
    (net (code "49") (name "TX") (class "Default")
      (node (ref "TP1") (pin "TP") (pinfunction "TP_TP") (pintype "input"))
      (node (ref "U2") (pin "25") (pinfunction "TXD0/GPIO16_25") (pintype "bidirectional"))
    )
    (net (code "50") (name "USB_D+") (class "Default")
      (node (ref "D1") (pin "1") (pinfunction "I/O1_1_1") (pintype "bidirectional"))
      (node (ref "U2") (pin "14") (pinfunction "IO13_14") (pintype "bidirectional"))
    )
    (net (code "51") (name "USB_D-") (class "Default")
      (node (ref "D1") (pin "3") (pinfunction "I/O2_1_3") (pintype "bidirectional"))
      (node (ref "U2") (pin "13") (pinfunction "IO12_13") (pintype "bidirectional"))
    )
    (net (code "52") (name "VBAT") (class "Default")
      (node (ref "C2_BAT") (pin "1") (pinfunction "1_1") (pintype "passive"))
      (node (ref "MCP73831") (pin "3") (pinfunction "VBAT_3") (pintype "power_in"))
      (node (ref "Q1") (pin "3") (pinfunction "D_3") (pintype "bidirectional"))
      (node (ref "TP3") (pin "TP") (pinfunction "TP_TP") (pintype "input"))
      (node (ref "U4") (pin "2") (pinfunction "CELL_2") (pintype "power_in"))
      (node (ref "U4") (pin "3") (pinfunction "VDD_3") (pintype "power_in"))
    )
    (net (code "53") (name "VBUS") (class "Default")
      (node (ref "C1_BAT") (pin "1") (pinfunction "1_1") (pintype "passive"))
      (node (ref "C1_USB") (pin "1") (pinfunction "1_1") (pintype "passive"))
      (node (ref "C2_USB") (pin "1") (pinfunction "1_1") (pintype "passive"))
      (node (ref "CHG_LED") (pin "A") (pinfunction "A_A") (pintype "passive"))
      (node (ref "D1") (pin "5") (pinfunction "VBUS_5") (pintype "bidirectional"))
      (node (ref "D2") (pin "2") (pinfunction "ANODE_2") (pintype "bidirectional"))
      (node (ref "MCP73831") (pin "4") (pinfunction "VIN_4") (pintype "power_in"))
      (node (ref "PFMF.050.1") (pin "2") (pinfunction "2_2") (pintype "passive"))
      (node (ref "Q1") (pin "1") (pinfunction "G_1") (pintype "bidirectional"))
      (node (ref "R1_PWRUSB") (pin "2") (pinfunction "2_2") (pintype "passive"))
      (node (ref "TP14") (pin "TP") (pinfunction "TP_TP") (pintype "input"))
    )
    (net (code "54") (name "VRTC") (class "Default")
      (node (ref "C10_SUPERCAP") (pin "2") (pinfunction "2_2") (pintype "passive"))
      (node (ref "C8") (pin "1") (pinfunction "1_1") (pintype "passive"))
      (node (ref "R_CAPACITOR") (pin "1") (pinfunction "1_1") (pintype "passive"))
      (node (ref "U3") (pin "14") (pinfunction "VBAT_14") (pintype "power_in"))
    )
    (net (code "55") (name "VUSB") (class "Default")
      (node (ref "J2") (pin "A4") (pinfunction "A4_A4") (pintype "bidirectional"))
      (node (ref "J2") (pin "A9") (pinfunction "A9_A9") (pintype "bidirectional"))
      (node (ref "J2") (pin "B4") (pinfunction "B4_B4") (pintype "bidirectional"))
      (node (ref "J2") (pin "B9") (pinfunction "B9_B9") (pintype "bidirectional"))
      (node (ref "PFMF.050.1") (pin "1") (pinfunction "1_1") (pintype "passive"))
    )
    (net (code "56") (name "unconnected-(IC1-NC-Pad4)") (class "Default")
      (node (ref "IC1") (pin "4") (pinfunction "NC_4") (pintype "no_connect"))
    )
    (net (code "57") (name "unconnected-(IC1-VOUT-Pad1)") (class "Default")
      (node (ref "IC1") (pin "1") (pinfunction "VOUT_1") (pintype "bidirectional"))
    )
    (net (code "58") (name "unconnected-(IC4-NC-Pad4)") (class "Default")
      (node (ref "IC4") (pin "4") (pinfunction "NC_4") (pintype "no_connect"))
    )
    (net (code "59") (name "unconnected-(J1-Pad1)") (class "Default")
      (node (ref "J1") (pin "1") (pinfunction "1_1") (pintype "bidirectional"))
    )
    (net (code "60") (name "unconnected-(J1-Pad6)") (class "Default")
      (node (ref "J1") (pin "6") (pinfunction "6_6") (pintype "bidirectional"))
    )
    (net (code "61") (name "unconnected-(J1-Pad7)") (class "Default")
      (node (ref "J1") (pin "7") (pinfunction "7_7") (pintype "bidirectional"))
    )
    (net (code "62") (name "unconnected-(J2-PadA8)") (class "Default")
      (node (ref "J2") (pin "A8") (pinfunction "A8_A8") (pintype "bidirectional"))
    )
    (net (code "63") (name "unconnected-(J2-PadB8)") (class "Default")
      (node (ref "J2") (pin "B8") (pinfunction "B8_B8") (pintype "bidirectional"))
    )
    (net (code "64") (name "unconnected-(J4-DAT1-PadP8)") (class "Default")
      (node (ref "J4") (pin "P8") (pinfunction "DAT1_P8") (pintype "bidirectional"))
    )
    (net (code "65") (name "unconnected-(J4-DAT2-PadP1)") (class "Default")
      (node (ref "J4") (pin "P1") (pinfunction "DAT2_P1") (pintype "bidirectional"))
    )
    (net (code "66") (name "unconnected-(J4-DETECTION_1-PadS1)") (class "Default")
      (node (ref "J4") (pin "S1") (pinfunction "DETECTION_1_S1") (pintype "bidirectional"))
    )
    (net (code "67") (name "unconnected-(J4-DETECTION_2-PadS2)") (class "Default")
      (node (ref "J4") (pin "S2") (pinfunction "DETECTION_2_S2") (pintype "bidirectional"))
    )
    (net (code "68") (name "unconnected-(U2-NC-Pad22)") (class "Default")
      (node (ref "U2") (pin "22") (pinfunction "NC_22") (pintype "no_connect"))
    )
    (net (code "69") (name "unconnected-(U4-~{ALERT}-Pad5)") (class "Default")
      (node (ref "U4") (pin "5") (pinfunction "~{ALERT}_5") (pintype "output"))
    )
  )
)
